# POWER_SUPPLY.net
KiCad netlist of a schematic drawn in Altium Designer
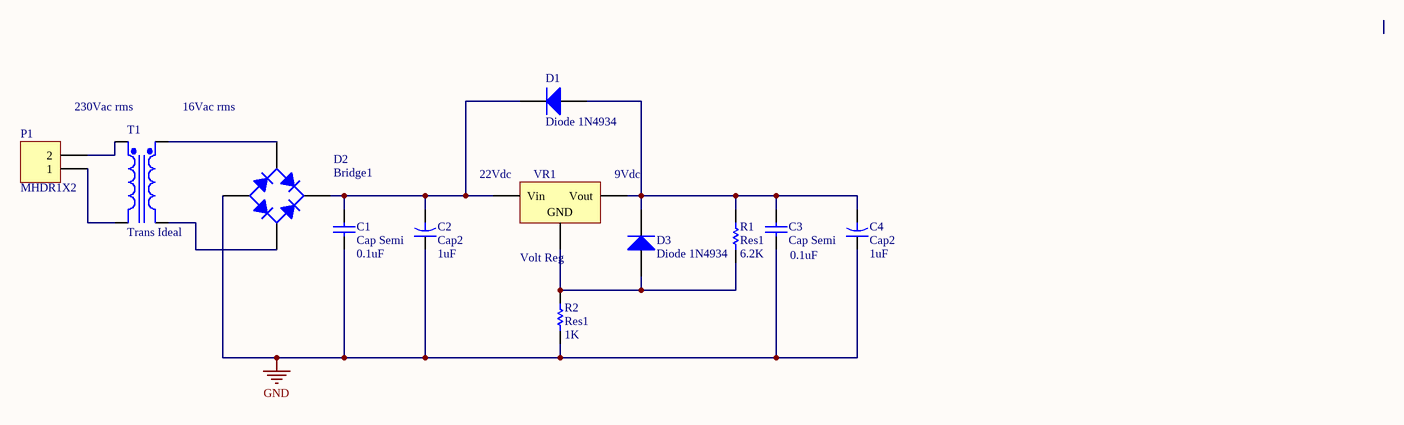
[diagram p0: POWER SUPPLY.SchDoc]

(export (version "E")
  (design (tool "Eeschema 10.0.6"))
  (components
    (comp (ref "C1")
      (value "Cap Semi")
      (footprint "C1206")
      (description "Capacitor (Semiconductor SIM Model)")
      (fields (field (name "ALTIUM_VALUE") "0.1uF") (field (name "PUBLISHER") "Altium Limited"))
      (libsource (lib "Miscellaneous Devices") (part "Cap Semi"))
    )
    (comp (ref "C2")
      (value "Cap2")
      (footprint "CAPR5-4X5")
      (description "Capacitor")
      (fields (field (name "ALTIUM_VALUE") "1uF") (field (name "PUBLISHER") "Altium Limited"))
      (libsource (lib "Miscellaneous Devices") (part "Cap2"))
    )
    (comp (ref "C3")
      (value "Cap Semi")
      (footprint "C1206")
      (description "Capacitor (Semiconductor SIM Model)")
      (fields (field (name "ALTIUM_VALUE") "0.1uF") (field (name "PUBLISHER") "Altium Limited"))
      (libsource (lib "Miscellaneous Devices") (part "Cap Semi"))
    )
    (comp (ref "C4")
      (value "Cap2")
      (footprint "CAPR5-4X5")
      (description "Capacitor")
      (fields (field (name "ALTIUM_VALUE") "1uF") (field (name "PUBLISHER") "Altium Limited"))
      (libsource (lib "Miscellaneous Devices") (part "Cap2"))
    )
    (comp (ref "D1")
      (value "Diode 1N4934")
      (footprint "DO-41")
      (description "1 Amp Fast Recovery Rectifier")
      (fields (field (name "PUBLISHER") "Altium Limited"))
      (libsource (lib "Miscellaneous Devices") (part "Diode 1N4934"))
    )
    (comp (ref "D2")
      (value "Bridge1")
      (footprint "D-38")
      (description "Full Wave Diode Bridge")
      (fields (field (name "PUBLISHER") "Altium Limited"))
      (libsource (lib "Miscellaneous Devices") (part "Bridge1"))
    )
    (comp (ref "D3")
      (value "Diode 1N4934")
      (footprint "DO-41")
      (description "1 Amp Fast Recovery Rectifier")
      (fields (field (name "PUBLISHER") "Altium Limited"))
      (libsource (lib "Miscellaneous Devices") (part "Diode 1N4934"))
    )
    (comp (ref "P1")
      (value "MHDR1X2")
      (footprint "MHDR1X2")
      (description "Header, 2-Pin")
      (fields (field (name "PUBLISHER") "Altium Limited"))
      (libsource (lib "Miscellaneous Connectors") (part "MHDR1X2"))
    )
    (comp (ref "R1")
      (value "Res1")
      (footprint "AXIAL-0.3")
      (description "Resistor")
      (fields (field (name "ALTIUM_VALUE") "6.2K") (field (name "PUBLISHER") "Altium Limited"))
      (libsource (lib "Miscellaneous Devices") (part "Res1"))
    )
    (comp (ref "R2")
      (value "Res1")
      (footprint "AXIAL-0.3")
      (description "Resistor")
      (fields (field (name "ALTIUM_VALUE") "1K") (field (name "PUBLISHER") "Altium Limited"))
      (libsource (lib "Miscellaneous Devices") (part "Res1"))
    )
    (comp (ref "T1")
      (value "Trans Ideal")
      (footprint "TRF_4")
      (description "Transformer (Ideal)")
      (fields (field (name "PUBLISHER") "Altium Limited"))
      (libsource (lib "Miscellaneous Devices") (part "Trans Ideal"))
    )
    (comp (ref "VR1")
      (value "Volt Reg")
      (footprint "D2PAK_N")
      (description "Voltage Regulator")
      (fields (field (name "PUBLISHER") "Altium Limited"))
      (libsource (lib "Miscellaneous Devices") (part "Volt Reg"))
    )
  )
  (nets
    (net (code "1") (name "GND") (class "Default")
      (node (ref "C1") (pin "1") (pinfunction "1_1") (pintype "passive"))
      (node (ref "C2") (pin "1") (pinfunction "1_1") (pintype "passive"))
      (node (ref "C3") (pin "1") (pinfunction "1_1") (pintype "passive"))
      (node (ref "C4") (pin "1") (pinfunction "1_1") (pintype "passive"))
      (node (ref "D2") (pin "3") (pinfunction "A_3") (pintype "passive"))
      (node (ref "R2") (pin "1") (pinfunction "1_1") (pintype "passive"))
    )
    (net (code "2") (name "Net-(D1-A)") (class "Default")
      (node (ref "C3") (pin "2") (pinfunction "2_2") (pintype "passive"))
      (node (ref "C4") (pin "2") (pinfunction "2_2") (pintype "passive"))
      (node (ref "D1") (pin "1") (pinfunction "A_1") (pintype "passive"))
      (node (ref "D3") (pin "2") (pinfunction "K_2") (pintype "passive"))
      (node (ref "R1") (pin "1") (pinfunction "1_1") (pintype "passive"))
      (node (ref "VR1") (pin "3") (pinfunction "Vout_3") (pintype "passive"))
    )
    (net (code "3") (name "Net-(D1-K)") (class "Default")
      (node (ref "C1") (pin "2") (pinfunction "2_2") (pintype "passive"))
      (node (ref "C2") (pin "2") (pinfunction "2_2") (pintype "passive"))
      (node (ref "D1") (pin "2") (pinfunction "K_2") (pintype "passive"))
      (node (ref "D2") (pin "1") (pinfunction "K_1") (pintype "passive"))
      (node (ref "VR1") (pin "1") (pinfunction "Vin_1") (pintype "passive"))
    )
    (net (code "4") (name "Net-(D3-A)") (class "Default")
      (node (ref "D3") (pin "1") (pinfunction "A_1") (pintype "passive"))
      (node (ref "R1") (pin "2") (pinfunction "2_2") (pintype "passive"))
      (node (ref "R2") (pin "2") (pinfunction "2_2") (pintype "passive"))
      (node (ref "VR1") (pin "2") (pinfunction "GND_2") (pintype "passive"))
    )
    (net (code "5") (name "Net-(T1-Pri+)") (class "Default")
      (node (ref "P1") (pin "2") (pinfunction "2_2") (pintype "passive"))
      (node (ref "T1") (pin "1") (pinfunction "Pri+_1") (pintype "passive"))
    )
    (net (code "6") (name "Net-(T1-Pri-)") (class "Default")
      (node (ref "P1") (pin "1") (pinfunction "1_1") (pintype "passive"))
      (node (ref "T1") (pin "2") (pinfunction "Pri-_2") (pintype "passive"))
    )
    (net (code "7") (name "Net-(T1-Sec+)") (class "Default")
      (node (ref "D2") (pin "4") (pinfunction "C_4") (pintype "passive"))
      (node (ref "T1") (pin "3") (pinfunction "Sec+_3") (pintype "passive"))
    )
    (net (code "8") (name "Net-(T1-Sec-)") (class "Default")
      (node (ref "D2") (pin "2") (pinfunction "C_2") (pintype "passive"))
      (node (ref "T1") (pin "4") (pinfunction "Sec-_4") (pintype "passive"))
    )
  )
)
